# SCREW.net
KiCad netlist of a schematic drawn in EAGLE
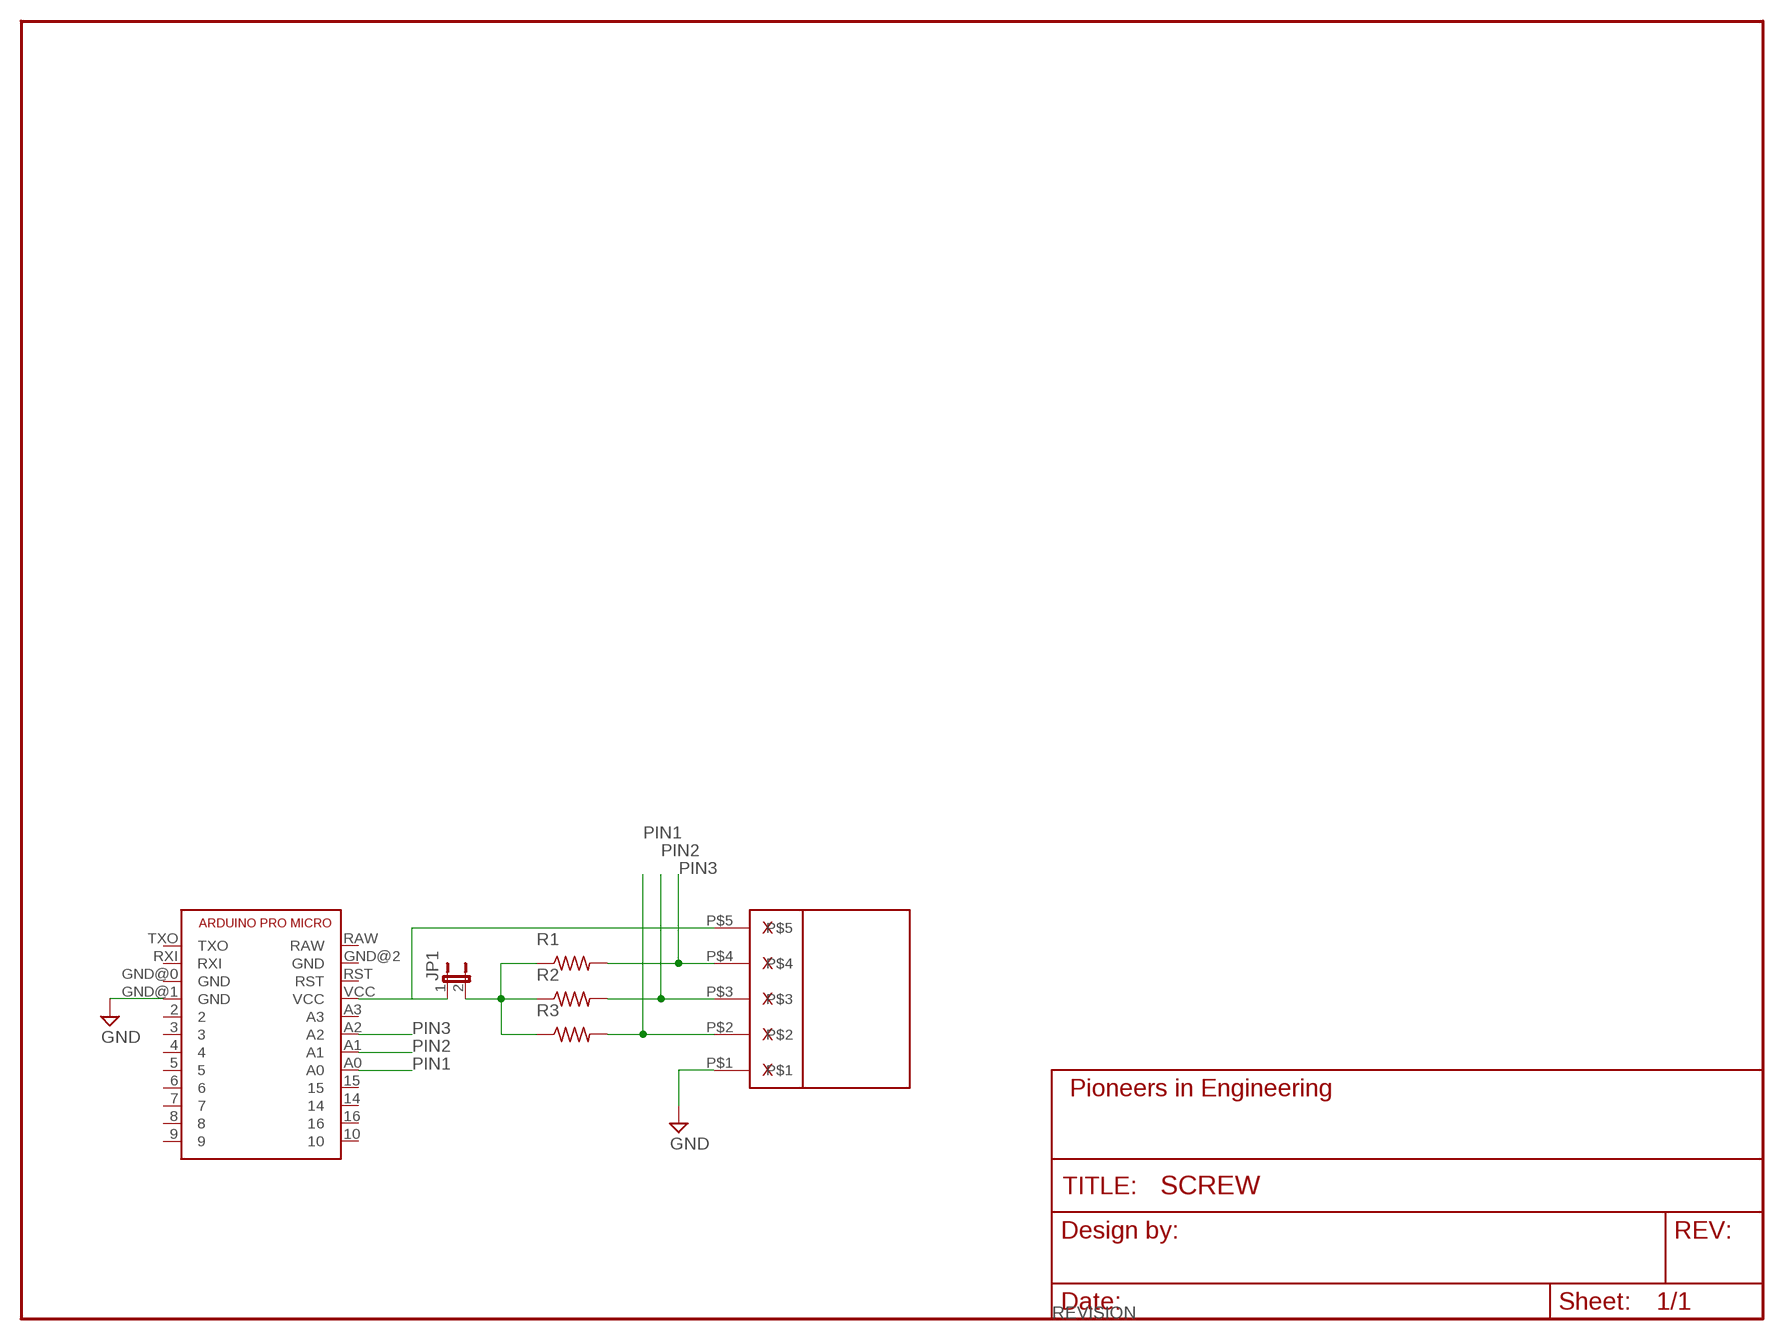
[diagram p0: schematic, sheet 1]

(export (version "E")
  (design (tool "Eeschema 10.0.6"))
  (components
    (comp (ref "JP1")
      (value "JP1E")
      (footprint "eagle-import:JP1")
      (libsource (lib "eagle-import") (part "JP1E"))
    )
    (comp (ref "R1")
      (value "R-US_R0603")
      (footprint "eagle-import:R0603")
      (libsource (lib "eagle-import") (part "R-US_R0603"))
    )
    (comp (ref "R2")
      (value "R-US_R0603")
      (footprint "eagle-import:R0603")
      (libsource (lib "eagle-import") (part "R-US_R0603"))
    )
    (comp (ref "R3")
      (value "R-US_R0603")
      (footprint "eagle-import:R0603")
      (libsource (lib "eagle-import") (part "R-US_R0603"))
    )
    (comp (ref "U$1")
      (value "5PIN_SCREW")
      (footprint "eagle-import:5PIN_SCREW")
      (libsource (lib "eagle-import") (part "5PIN_SCREW"))
    )
    (comp (ref "U$2")
      (value "ARDUINO_PRO_MICRO")
      (footprint "eagle-import:ARDUINO_PRO_MICRO")
      (libsource (lib "eagle-import") (part "ARDUINO_PRO_MICRO"))
    )
  )
  (nets
    (net (code "1") (name "/PIN1") (class "Default")
      (node (ref "R3") (pin "2") (pinfunction "2_2") (pintype "passive"))
      (node (ref "U$1") (pin "P$2") (pinfunction "P$2_P$2") (pintype "bidirectional"))
      (node (ref "U$2") (pin "A0") (pinfunction "A0_A0") (pintype "bidirectional"))
    )
    (net (code "2") (name "/PIN2") (class "Default")
      (node (ref "R2") (pin "2") (pinfunction "2_2") (pintype "passive"))
      (node (ref "U$1") (pin "P$3") (pinfunction "P$3_P$3") (pintype "bidirectional"))
      (node (ref "U$2") (pin "A1") (pinfunction "A1_A1") (pintype "bidirectional"))
    )
    (net (code "3") (name "/PIN3") (class "Default")
      (node (ref "R1") (pin "2") (pinfunction "2_2") (pintype "passive"))
      (node (ref "U$1") (pin "P$4") (pinfunction "P$4_P$4") (pintype "bidirectional"))
      (node (ref "U$2") (pin "A2") (pinfunction "A2_A2") (pintype "bidirectional"))
    )
    (net (code "4") (name "GND") (class "Default")
      (node (ref "U$1") (pin "P$1") (pinfunction "P$1_P$1") (pintype "bidirectional"))
      (node (ref "U$2") (pin "GND@1") (pinfunction "GND_GND@1") (pintype "bidirectional"))
    )
    (net (code "5") (name "Net-(JP1-Pad1)") (class "Default")
      (node (ref "JP1") (pin "1") (pinfunction "1_1") (pintype "passive"))
      (node (ref "U$1") (pin "P$5") (pinfunction "P$5_P$5") (pintype "bidirectional"))
      (node (ref "U$2") (pin "VCC") (pinfunction "VCC_VCC") (pintype "bidirectional"))
    )
    (net (code "6") (name "Net-(JP1-Pad2)") (class "Default")
      (node (ref "JP1") (pin "2") (pinfunction "2_2") (pintype "passive"))
      (node (ref "R1") (pin "1") (pinfunction "1_1") (pintype "passive"))
      (node (ref "R2") (pin "1") (pinfunction "1_1") (pintype "passive"))
      (node (ref "R3") (pin "1") (pinfunction "1_1") (pintype "passive"))
    )
    (net (code "7") (name "unconnected-(U$2-GND-PadGND@0)") (class "Default")
      (node (ref "U$2") (pin "GND@0") (pinfunction "GND_GND@0") (pintype "bidirectional"))
    )
    (net (code "8") (name "unconnected-(U$2-GND-PadGND@2)") (class "Default")
      (node (ref "U$2") (pin "GND@2") (pinfunction "GND_GND@2") (pintype "bidirectional"))
    )
    (net (code "9") (name "unconnected-(U$2-Pad2)") (class "Default")
      (node (ref "U$2") (pin "2") (pinfunction "2_2") (pintype "bidirectional"))
    )
    (net (code "10") (name "unconnected-(U$2-Pad3)") (class "Default")
      (node (ref "U$2") (pin "3") (pinfunction "3_3") (pintype "bidirectional"))
    )
    (net (code "11") (name "unconnected-(U$2-Pad4)") (class "Default")
      (node (ref "U$2") (pin "4") (pinfunction "4_4") (pintype "bidirectional"))
    )
    (net (code "12") (name "unconnected-(U$2-Pad5)") (class "Default")
      (node (ref "U$2") (pin "5") (pinfunction "5_5") (pintype "bidirectional"))
    )
    (net (code "13") (name "unconnected-(U$2-Pad6)") (class "Default")
      (node (ref "U$2") (pin "6") (pinfunction "6_6") (pintype "bidirectional"))
    )
    (net (code "14") (name "unconnected-(U$2-Pad7)") (class "Default")
      (node (ref "U$2") (pin "7") (pinfunction "7_7") (pintype "bidirectional"))
    )
    (net (code "15") (name "unconnected-(U$2-Pad8)") (class "Default")
      (node (ref "U$2") (pin "8") (pinfunction "8_8") (pintype "bidirectional"))
    )
    (net (code "16") (name "unconnected-(U$2-Pad9)") (class "Default")
      (node (ref "U$2") (pin "9") (pinfunction "9_9") (pintype "bidirectional"))
    )
    (net (code "17") (name "unconnected-(U$2-Pad10)") (class "Default")
      (node (ref "U$2") (pin "10") (pinfunction "10_10") (pintype "bidirectional"))
    )
    (net (code "18") (name "unconnected-(U$2-Pad14)") (class "Default")
      (node (ref "U$2") (pin "14") (pinfunction "14_14") (pintype "bidirectional"))
    )
    (net (code "19") (name "unconnected-(U$2-Pad15)") (class "Default")
      (node (ref "U$2") (pin "15") (pinfunction "15_15") (pintype "bidirectional"))
    )
    (net (code "20") (name "unconnected-(U$2-Pad16)") (class "Default")
      (node (ref "U$2") (pin "16") (pinfunction "16_16") (pintype "bidirectional"))
    )
    (net (code "21") (name "unconnected-(U$2-PadA3)") (class "Default")
      (node (ref "U$2") (pin "A3") (pinfunction "A3_A3") (pintype "bidirectional"))
    )
    (net (code "22") (name "unconnected-(U$2-PadRAW)") (class "Default")
      (node (ref "U$2") (pin "RAW") (pinfunction "RAW_RAW") (pintype "bidirectional"))
    )
    (net (code "23") (name "unconnected-(U$2-PadRST)") (class "Default")
      (node (ref "U$2") (pin "RST") (pinfunction "RST_RST") (pintype "bidirectional"))
    )
    (net (code "24") (name "unconnected-(U$2-PadRXI)") (class "Default")
      (node (ref "U$2") (pin "RXI") (pinfunction "RXI_RXI") (pintype "bidirectional"))
    )
    (net (code "25") (name "unconnected-(U$2-PadTXO)") (class "Default")
      (node (ref "U$2") (pin "TXO") (pinfunction "TXO_TXO") (pintype "bidirectional"))
    )
  )
)
